# wire.net
KiCad netlist of a schematic drawn in EAGLE
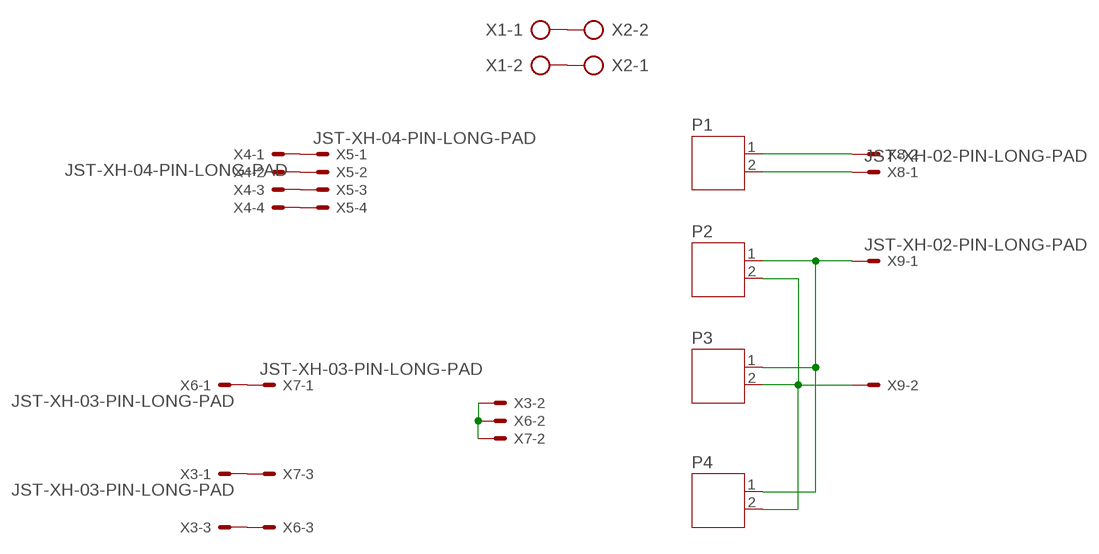
[diagram p0: schematic, sheet 1]

(export (version "E")
  (design (tool "Eeschema 10.0.6"))
  (components
    (comp (ref "P1")
      (value "JST-PH2")
      (footprint "eagle-import:JST-PH2")
      (libsource (lib "eagle-import") (part "JST-PH2"))
    )
    (comp (ref "P2")
      (value "JST-PH2")
      (footprint "eagle-import:JST-PH2")
      (libsource (lib "eagle-import") (part "JST-PH2"))
    )
    (comp (ref "P3")
      (value "JST-PH2")
      (footprint "eagle-import:JST-PH2")
      (libsource (lib "eagle-import") (part "JST-PH2"))
    )
    (comp (ref "P4")
      (value "JST-PH2")
      (footprint "eagle-import:JST-PH2")
      (libsource (lib "eagle-import") (part "JST-PH2"))
    )
    (comp (ref "X1")
      (value "AK500/2")
      (footprint "eagle-import:AK500_2")
      (libsource (lib "eagle-import") (part "AK500/2"))
    )
    (comp (ref "X2")
      (value "AK500/2")
      (footprint "eagle-import:AK500_2")
      (libsource (lib "eagle-import") (part "AK500/2"))
    )
    (comp (ref "X3")
      (value "JST-XH-03-PIN-LONG-PAD")
      (footprint "eagle-import:JST-XH-03-PACKAGE-LONG-PAD")
      (libsource (lib "eagle-import") (part "JST-XH-03-PIN-LONG-PAD"))
    )
    (comp (ref "X4")
      (value "JST-XH-04-PIN-LONG-PAD")
      (footprint "eagle-import:JST-XH-04-PACKAGE-LONG-PAD")
      (libsource (lib "eagle-import") (part "JST-XH-04-PIN-LONG-PAD"))
    )
    (comp (ref "X5")
      (value "JST-XH-04-PIN-LONG-PAD")
      (footprint "eagle-import:JST-XH-04-PACKAGE-LONG-PAD")
      (libsource (lib "eagle-import") (part "JST-XH-04-PIN-LONG-PAD"))
    )
    (comp (ref "X6")
      (value "JST-XH-03-PIN-LONG-PAD")
      (footprint "eagle-import:JST-XH-03-PACKAGE-LONG-PAD")
      (libsource (lib "eagle-import") (part "JST-XH-03-PIN-LONG-PAD"))
    )
    (comp (ref "X7")
      (value "JST-XH-03-PIN-LONG-PAD")
      (footprint "eagle-import:JST-XH-03-PACKAGE-LONG-PAD")
      (libsource (lib "eagle-import") (part "JST-XH-03-PIN-LONG-PAD"))
    )
    (comp (ref "X8")
      (value "JST-XH-02-PIN-LONG-PAD")
      (footprint "eagle-import:JST-XH-02-PACKAGE-LONG-PAD")
      (libsource (lib "eagle-import") (part "JST-XH-02-PIN-LONG-PAD"))
    )
    (comp (ref "X9")
      (value "JST-XH-02-PIN-LONG-PAD")
      (footprint "eagle-import:JST-XH-02-PACKAGE-LONG-PAD")
      (libsource (lib "eagle-import") (part "JST-XH-02-PIN-LONG-PAD"))
    )
  )
  (nets
    (net (code "1") (name "Net-(X1A-KL)") (class "Default")
      (node (ref "X1") (pin "1") (pinfunction "KL_1") (pintype "passive"))
      (node (ref "X2") (pin "2") (pinfunction "KL_2") (pintype "passive"))
    )
    (net (code "2") (name "Net-(X1B-KL)") (class "Default")
      (node (ref "X1") (pin "2") (pinfunction "KL_2") (pintype "passive"))
      (node (ref "X2") (pin "1") (pinfunction "KL_1") (pintype "passive"))
    )
    (net (code "3") (name "Net-(X3A-S)") (class "Default")
      (node (ref "X3") (pin "1") (pinfunction "S_1") (pintype "passive"))
      (node (ref "X7") (pin "3") (pinfunction "S_3") (pintype "passive"))
    )
    (net (code "4") (name "Net-(X3B-S)") (class "Default")
      (node (ref "X3") (pin "2") (pinfunction "S_2") (pintype "passive"))
      (node (ref "X6") (pin "2") (pinfunction "S_2") (pintype "passive"))
      (node (ref "X7") (pin "2") (pinfunction "S_2") (pintype "passive"))
    )
    (net (code "5") (name "Net-(X3C-S)") (class "Default")
      (node (ref "X3") (pin "3") (pinfunction "S_3") (pintype "passive"))
      (node (ref "X6") (pin "3") (pinfunction "S_3") (pintype "passive"))
    )
    (net (code "6") (name "Net-(X4A-S)") (class "Default")
      (node (ref "X4") (pin "1") (pinfunction "S_1") (pintype "passive"))
      (node (ref "X5") (pin "1") (pinfunction "S_1") (pintype "passive"))
    )
    (net (code "7") (name "Net-(X4B-S)") (class "Default")
      (node (ref "X4") (pin "2") (pinfunction "S_2") (pintype "passive"))
      (node (ref "X5") (pin "2") (pinfunction "S_2") (pintype "passive"))
    )
    (net (code "8") (name "Net-(X4C-S)") (class "Default")
      (node (ref "X4") (pin "3") (pinfunction "S_3") (pintype "passive"))
      (node (ref "X5") (pin "3") (pinfunction "S_3") (pintype "passive"))
    )
    (net (code "9") (name "Net-(X4D-S)") (class "Default")
      (node (ref "X4") (pin "4") (pinfunction "S_4") (pintype "passive"))
      (node (ref "X5") (pin "4") (pinfunction "S_4") (pintype "passive"))
    )
    (net (code "10") (name "Net-(X6A-S)") (class "Default")
      (node (ref "X6") (pin "1") (pinfunction "S_1") (pintype "passive"))
      (node (ref "X7") (pin "1") (pinfunction "S_1") (pintype "passive"))
    )
    (net (code "11") (name "Net-(X8A-S)") (class "Default")
      (node (ref "P1") (pin "2") (pinfunction "2_2") (pintype "passive"))
      (node (ref "X8") (pin "1") (pinfunction "S_1") (pintype "passive"))
    )
    (net (code "12") (name "Net-(X8B-S)") (class "Default")
      (node (ref "P1") (pin "1") (pinfunction "1_1") (pintype "passive"))
      (node (ref "X8") (pin "2") (pinfunction "S_2") (pintype "passive"))
    )
    (net (code "13") (name "Net-(X9A-S)") (class "Default")
      (node (ref "P2") (pin "1") (pinfunction "1_1") (pintype "passive"))
      (node (ref "P3") (pin "1") (pinfunction "1_1") (pintype "passive"))
      (node (ref "P4") (pin "1") (pinfunction "1_1") (pintype "passive"))
      (node (ref "X9") (pin "1") (pinfunction "S_1") (pintype "passive"))
    )
    (net (code "14") (name "Net-(X9B-S)") (class "Default")
      (node (ref "P2") (pin "2") (pinfunction "2_2") (pintype "passive"))
      (node (ref "P3") (pin "2") (pinfunction "2_2") (pintype "passive"))
      (node (ref "P4") (pin "2") (pinfunction "2_2") (pintype "passive"))
      (node (ref "X9") (pin "2") (pinfunction "S_2") (pintype "passive"))
    )
  )
)
